# asomator5.net
KiCad netlist of a schematic drawn in EAGLE
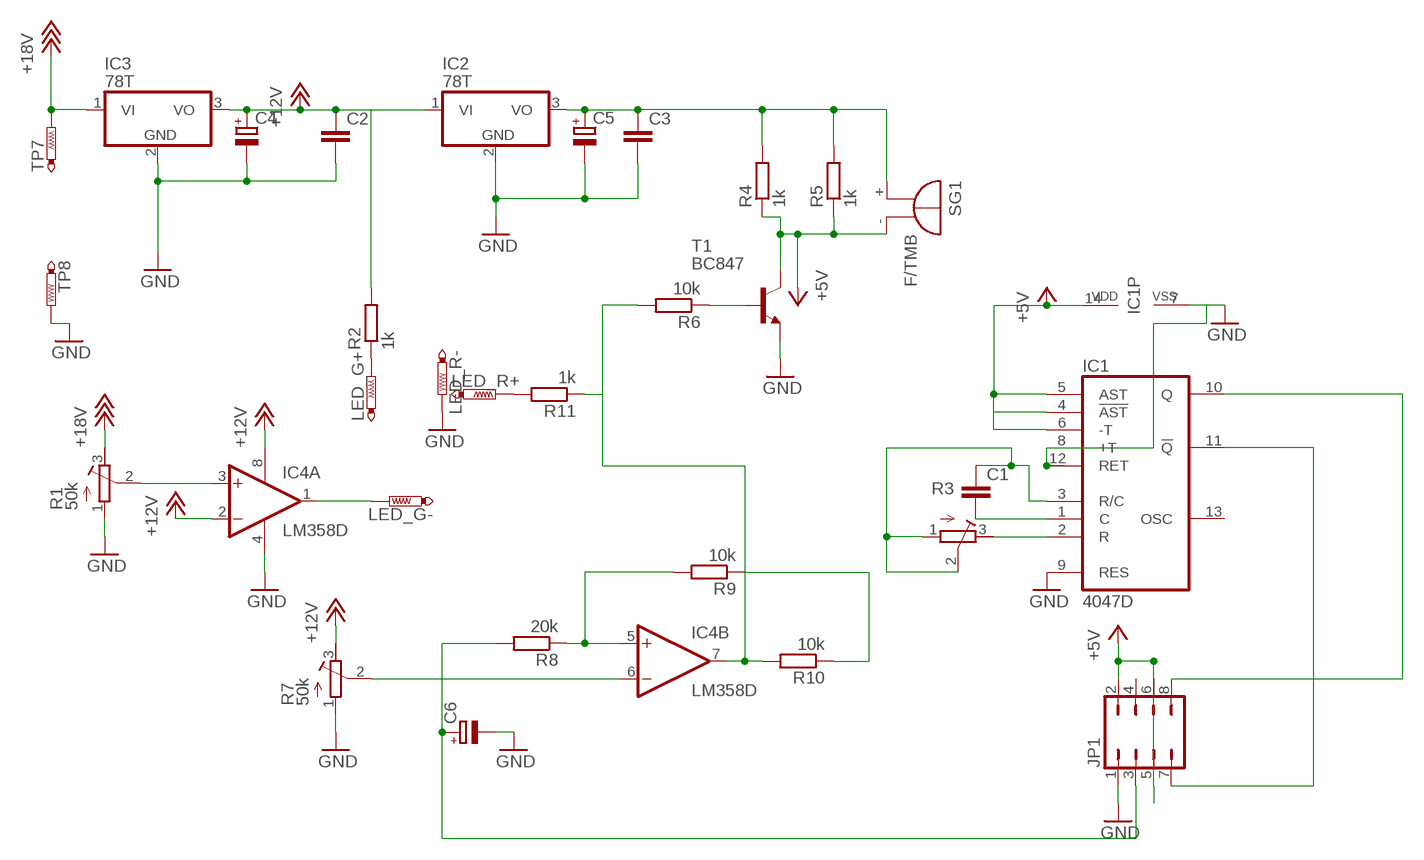
[diagram p0: schematic, sheet 1]

(export (version "E")
  (design (tool "Eeschema 10.0.6"))
  (components
    (comp (ref "C1")
      (value "C-EUC1210")
      (footprint "eagle-import:C1210")
      (libsource (lib "eagle-import") (part "C-EUC1210"))
    )
    (comp (ref "C2")
      (value "C-EUC1210")
      (footprint "eagle-import:C1210")
      (libsource (lib "eagle-import") (part "C-EUC1210"))
    )
    (comp (ref "C3")
      (value "C-EUC1210")
      (footprint "eagle-import:C1210")
      (libsource (lib "eagle-import") (part "C-EUC1210"))
    )
    (comp (ref "C4")
      (value "CPOL-EUE2.5-7")
      (footprint "eagle-import:E2,5-7")
      (libsource (lib "eagle-import") (part "CPOL-EUE2.5-7"))
    )
    (comp (ref "C5")
      (value "CPOL-EUE2.5-7")
      (footprint "eagle-import:E2,5-7")
      (libsource (lib "eagle-import") (part "CPOL-EUE2.5-7"))
    )
    (comp (ref "C6")
      (value "CPOL-EUE2.5-7")
      (footprint "eagle-import:E2,5-7")
      (libsource (lib "eagle-import") (part "CPOL-EUE2.5-7"))
    )
    (comp (ref "IC1")
      (value "4047D")
      (footprint "eagle-import:SO14")
      (libsource (lib "eagle-import") (part "4047D"))
    )
    (comp (ref "IC2")
      (value "78T")
      (footprint "eagle-import:TO220H")
      (libsource (lib "eagle-import") (part "78T05"))
    )
    (comp (ref "IC3")
      (value "78T")
      (footprint "eagle-import:TO220H")
      (libsource (lib "eagle-import") (part "78T12"))
    )
    (comp (ref "IC4")
      (value "LM358D")
      (footprint "eagle-import:SO08")
      (libsource (lib "eagle-import") (part "LM358D"))
    )
    (comp (ref "JP1")
      (value "JP4Q")
      (footprint "eagle-import:JP4Q")
      (libsource (lib "eagle-import") (part "JP4Q"))
    )
    (comp (ref "LED_G+")
      (value "PTR1PAD1-13Y")
      (footprint "eagle-import:P1-13Y")
      (libsource (lib "eagle-import") (part "PTR1PAD1-13Y"))
    )
    (comp (ref "LED_G-")
      (value "PTR1PAD1-13Y")
      (footprint "eagle-import:P1-13Y")
      (libsource (lib "eagle-import") (part "PTR1PAD1-13Y"))
    )
    (comp (ref "LED_R+")
      (value "PTR1PAD1-13Y")
      (footprint "eagle-import:P1-13Y")
      (libsource (lib "eagle-import") (part "PTR1PAD1-13Y"))
    )
    (comp (ref "LED_R-")
      (value "PTR1PAD1-13Y")
      (footprint "eagle-import:P1-13Y")
      (libsource (lib "eagle-import") (part "PTR1PAD1-13Y"))
    )
    (comp (ref "R1")
      (value "50k")
      (footprint "eagle-import:RTRIM64W")
      (libsource (lib "eagle-import") (part "R-TRIMM64W"))
    )
    (comp (ref "R2")
      (value "1k")
      (footprint "eagle-import:R1206")
      (libsource (lib "eagle-import") (part "R-EU_R1206"))
    )
    (comp (ref "R3")
      (value "R-TRIMM4G/J")
      (footprint "eagle-import:RTRIM4G_J")
      (libsource (lib "eagle-import") (part "R-TRIMM4G/J"))
    )
    (comp (ref "R4")
      (value "1k")
      (footprint "eagle-import:R1206")
      (libsource (lib "eagle-import") (part "R-EU_R1206"))
    )
    (comp (ref "R5")
      (value "1k")
      (footprint "eagle-import:R1206")
      (libsource (lib "eagle-import") (part "R-EU_R1206"))
    )
    (comp (ref "R6")
      (value "10k")
      (footprint "eagle-import:R1206")
      (libsource (lib "eagle-import") (part "R-EU_R1206"))
    )
    (comp (ref "R7")
      (value "50k")
      (footprint "eagle-import:RTRIM64W")
      (libsource (lib "eagle-import") (part "R-TRIMM64W"))
    )
    (comp (ref "R8")
      (value "20k")
      (footprint "eagle-import:R1206")
      (libsource (lib "eagle-import") (part "R-EU_R1206"))
    )
    (comp (ref "R9")
      (value "10k")
      (footprint "eagle-import:R1206")
      (libsource (lib "eagle-import") (part "R-EU_R1206"))
    )
    (comp (ref "R10")
      (value "10k")
      (footprint "eagle-import:R1206")
      (libsource (lib "eagle-import") (part "R-EU_R1206"))
    )
    (comp (ref "R11")
      (value "1k")
      (footprint "eagle-import:R1206")
      (libsource (lib "eagle-import") (part "R-EU_R1206"))
    )
    (comp (ref "SG1")
      (value "F/TMB")
      (footprint "eagle-import:F_TMB")
      (libsource (lib "eagle-import") (part "F/TMB"))
    )
    (comp (ref "T1")
      (value "BC847")
      (footprint "eagle-import:SOT23")
      (libsource (lib "eagle-import") (part "BC847"))
    )
    (comp (ref "TP7")
      (value "PTR1PAD1-13Y")
      (footprint "eagle-import:P1-13Y")
      (libsource (lib "eagle-import") (part "PTR1PAD1-13Y"))
    )
    (comp (ref "TP8")
      (value "PTR1PAD1-13Y")
      (footprint "eagle-import:P1-13Y")
      (libsource (lib "eagle-import") (part "PTR1PAD1-13Y"))
    )
  )
  (nets
    (net (code "1") (name "+5V") (class "Default")
      (node (ref "IC1") (pin "14") (pinfunction "VDD_14") (pintype "power_in"))
      (node (ref "IC1") (pin "4") (pinfunction "~{AST}_4") (pintype "input"))
      (node (ref "IC1") (pin "5") (pinfunction "AST_5") (pintype "input"))
      (node (ref "IC1") (pin "6") (pinfunction "-T_6") (pintype "input"))
      (node (ref "JP1") (pin "2") (pinfunction "2_2") (pintype "passive"))
      (node (ref "JP1") (pin "5") (pinfunction "5_5") (pintype "passive"))
      (node (ref "JP1") (pin "6") (pinfunction "6_6") (pintype "passive"))
      (node (ref "R4") (pin "1") (pinfunction "1_1") (pintype "passive"))
      (node (ref "R5") (pin "1") (pinfunction "1_1") (pintype "passive"))
      (node (ref "SG1") (pin "-") (pinfunction "-_-") (pintype "passive"))
      (node (ref "T1") (pin "3") (pinfunction "C_3") (pintype "passive"))
    )
    (net (code "2") (name "+12V") (class "Default")
      (node (ref "C2") (pin "1") (pinfunction "1_1") (pintype "passive"))
      (node (ref "C4") (pin "+") (pinfunction "+_+") (pintype "passive"))
      (node (ref "IC2") (pin "1") (pinfunction "VI_1") (pintype "input"))
      (node (ref "IC3") (pin "3") (pinfunction "VO_3") (pintype "passive"))
      (node (ref "IC4") (pin "2") (pinfunction "-IN_2") (pintype "input"))
      (node (ref "IC4") (pin "8") (pinfunction "V+_8") (pintype "power_in"))
      (node (ref "R2") (pin "2") (pinfunction "2_2") (pintype "passive"))
      (node (ref "R7") (pin "3") (pinfunction "E_3") (pintype "passive"))
    )
    (net (code "3") (name "+18V") (class "Default")
      (node (ref "IC3") (pin "1") (pinfunction "VI_1") (pintype "input"))
      (node (ref "R1") (pin "3") (pinfunction "E_3") (pintype "passive"))
      (node (ref "TP7") (pin "TP") (pinfunction "TP_TP") (pintype "input"))
    )
    (net (code "4") (name "GND") (class "Default")
      (node (ref "C2") (pin "2") (pinfunction "2_2") (pintype "passive"))
      (node (ref "C3") (pin "2") (pinfunction "2_2") (pintype "passive"))
      (node (ref "C4") (pin "-") (pinfunction "-_-") (pintype "passive"))
      (node (ref "C5") (pin "-") (pinfunction "-_-") (pintype "passive"))
      (node (ref "C6") (pin "-") (pinfunction "-_-") (pintype "passive"))
      (node (ref "IC1") (pin "12") (pinfunction "RET_12") (pintype "input"))
      (node (ref "IC1") (pin "7") (pinfunction "VSS_7") (pintype "power_in"))
      (node (ref "IC1") (pin "8") (pinfunction "+T_8") (pintype "input"))
      (node (ref "IC1") (pin "9") (pinfunction "RES_9") (pintype "input"))
      (node (ref "IC2") (pin "2") (pinfunction "GND_2") (pintype "passive"))
      (node (ref "IC3") (pin "2") (pinfunction "GND_2") (pintype "passive"))
      (node (ref "IC4") (pin "4") (pinfunction "V-_4") (pintype "power_in"))
      (node (ref "JP1") (pin "1") (pinfunction "1_1") (pintype "passive"))
      (node (ref "LED_R-") (pin "TP") (pinfunction "TP_TP") (pintype "input"))
      (node (ref "R1") (pin "1") (pinfunction "A_1") (pintype "passive"))
      (node (ref "R7") (pin "1") (pinfunction "A_1") (pintype "passive"))
      (node (ref "T1") (pin "2") (pinfunction "E_2") (pintype "passive"))
      (node (ref "TP8") (pin "TP") (pinfunction "TP_TP") (pintype "input"))
    )
    (net (code "5") (name "Net-(C6-Pad+)") (class "Default")
      (node (ref "C6") (pin "+") (pinfunction "+_+") (pintype "passive"))
      (node (ref "JP1") (pin "3") (pinfunction "3_3") (pintype "passive"))
      (node (ref "R8") (pin "2") (pinfunction "2_2") (pintype "passive"))
    )
    (net (code "6") (name "Net-(IC1A-C)") (class "Default")
      (node (ref "C1") (pin "2") (pinfunction "2_2") (pintype "passive"))
      (node (ref "IC1") (pin "1") (pinfunction "C_1") (pintype "input"))
    )
    (net (code "7") (name "Net-(IC1A-Q)") (class "Default")
      (node (ref "IC1") (pin "10") (pinfunction "Q_10") (pintype "output"))
      (node (ref "JP1") (pin "8") (pinfunction "8_8") (pintype "passive"))
    )
    (net (code "8") (name "Net-(IC1A-R)") (class "Default")
      (node (ref "IC1") (pin "2") (pinfunction "R_2") (pintype "input"))
      (node (ref "R3") (pin "3") (pinfunction "E_3") (pintype "passive"))
    )
    (net (code "9") (name "Net-(IC1A-R{slash}C)") (class "Default")
      (node (ref "C1") (pin "1") (pinfunction "1_1") (pintype "passive"))
      (node (ref "IC1") (pin "3") (pinfunction "R/C_3") (pintype "input"))
      (node (ref "R3") (pin "1") (pinfunction "A_1") (pintype "passive"))
      (node (ref "R3") (pin "2") (pinfunction "S_2") (pintype "passive"))
    )
    (net (code "10") (name "Net-(IC1A-~{Q})") (class "Default")
      (node (ref "IC1") (pin "11") (pinfunction "~{Q}_11") (pintype "output"))
      (node (ref "JP1") (pin "7") (pinfunction "7_7") (pintype "passive"))
    )
    (net (code "11") (name "Net-(IC2-VO)") (class "Default")
      (node (ref "C3") (pin "1") (pinfunction "1_1") (pintype "passive"))
      (node (ref "C5") (pin "+") (pinfunction "+_+") (pintype "passive"))
      (node (ref "IC2") (pin "3") (pinfunction "VO_3") (pintype "passive"))
      (node (ref "R4") (pin "2") (pinfunction "2_2") (pintype "passive"))
      (node (ref "R5") (pin "2") (pinfunction "2_2") (pintype "passive"))
      (node (ref "SG1") (pin "+") (pinfunction "+_+") (pintype "passive"))
    )
    (net (code "12") (name "Net-(IC4A-+IN)") (class "Default")
      (node (ref "IC4") (pin "3") (pinfunction "+IN_3") (pintype "input"))
      (node (ref "R1") (pin "2") (pinfunction "S_2") (pintype "passive"))
    )
    (net (code "13") (name "Net-(IC4A-OUT)") (class "Default")
      (node (ref "IC4") (pin "1") (pinfunction "OUT_1") (pintype "output"))
      (node (ref "LED_G-") (pin "TP") (pinfunction "TP_TP") (pintype "input"))
    )
    (net (code "14") (name "Net-(IC4B-+IN)") (class "Default")
      (node (ref "IC4") (pin "5") (pinfunction "+IN_5") (pintype "input"))
      (node (ref "R8") (pin "1") (pinfunction "1_1") (pintype "passive"))
      (node (ref "R9") (pin "2") (pinfunction "2_2") (pintype "passive"))
    )
    (net (code "15") (name "Net-(IC4B--IN)") (class "Default")
      (node (ref "IC4") (pin "6") (pinfunction "-IN_6") (pintype "input"))
      (node (ref "R7") (pin "2") (pinfunction "S_2") (pintype "passive"))
    )
    (net (code "16") (name "Net-(IC4B-OUT)") (class "Default")
      (node (ref "IC4") (pin "7") (pinfunction "OUT_7") (pintype "output"))
      (node (ref "R10") (pin "2") (pinfunction "2_2") (pintype "passive"))
      (node (ref "R11") (pin "1") (pinfunction "1_1") (pintype "passive"))
      (node (ref "R6") (pin "2") (pinfunction "2_2") (pintype "passive"))
    )
    (net (code "17") (name "Net-(LED_G+-PadTP)") (class "Default")
      (node (ref "LED_G+") (pin "TP") (pinfunction "TP_TP") (pintype "input"))
      (node (ref "R2") (pin "1") (pinfunction "1_1") (pintype "passive"))
    )
    (net (code "18") (name "Net-(LED_R+-PadTP)") (class "Default")
      (node (ref "LED_R+") (pin "TP") (pinfunction "TP_TP") (pintype "input"))
      (node (ref "R11") (pin "2") (pinfunction "2_2") (pintype "passive"))
    )
    (net (code "19") (name "Net-(R10-Pad1)") (class "Default")
      (node (ref "R10") (pin "1") (pinfunction "1_1") (pintype "passive"))
      (node (ref "R9") (pin "1") (pinfunction "1_1") (pintype "passive"))
    )
    (net (code "20") (name "Net-(T1-B)") (class "Default")
      (node (ref "R6") (pin "1") (pinfunction "1_1") (pintype "passive"))
      (node (ref "T1") (pin "1") (pinfunction "B_1") (pintype "passive"))
    )
    (net (code "21") (name "unconnected-(IC1A-OSC-Pad13)") (class "Default")
      (node (ref "IC1") (pin "13") (pinfunction "OSC_13") (pintype "output"))
    )
    (net (code "22") (name "unconnected-(JP1-Pad4)") (class "Default")
      (node (ref "JP1") (pin "4") (pinfunction "4_4") (pintype "passive"))
    )
  )
)
